# PiHAT_v0_4.net
KiCad netlist of a schematic drawn in EAGLE
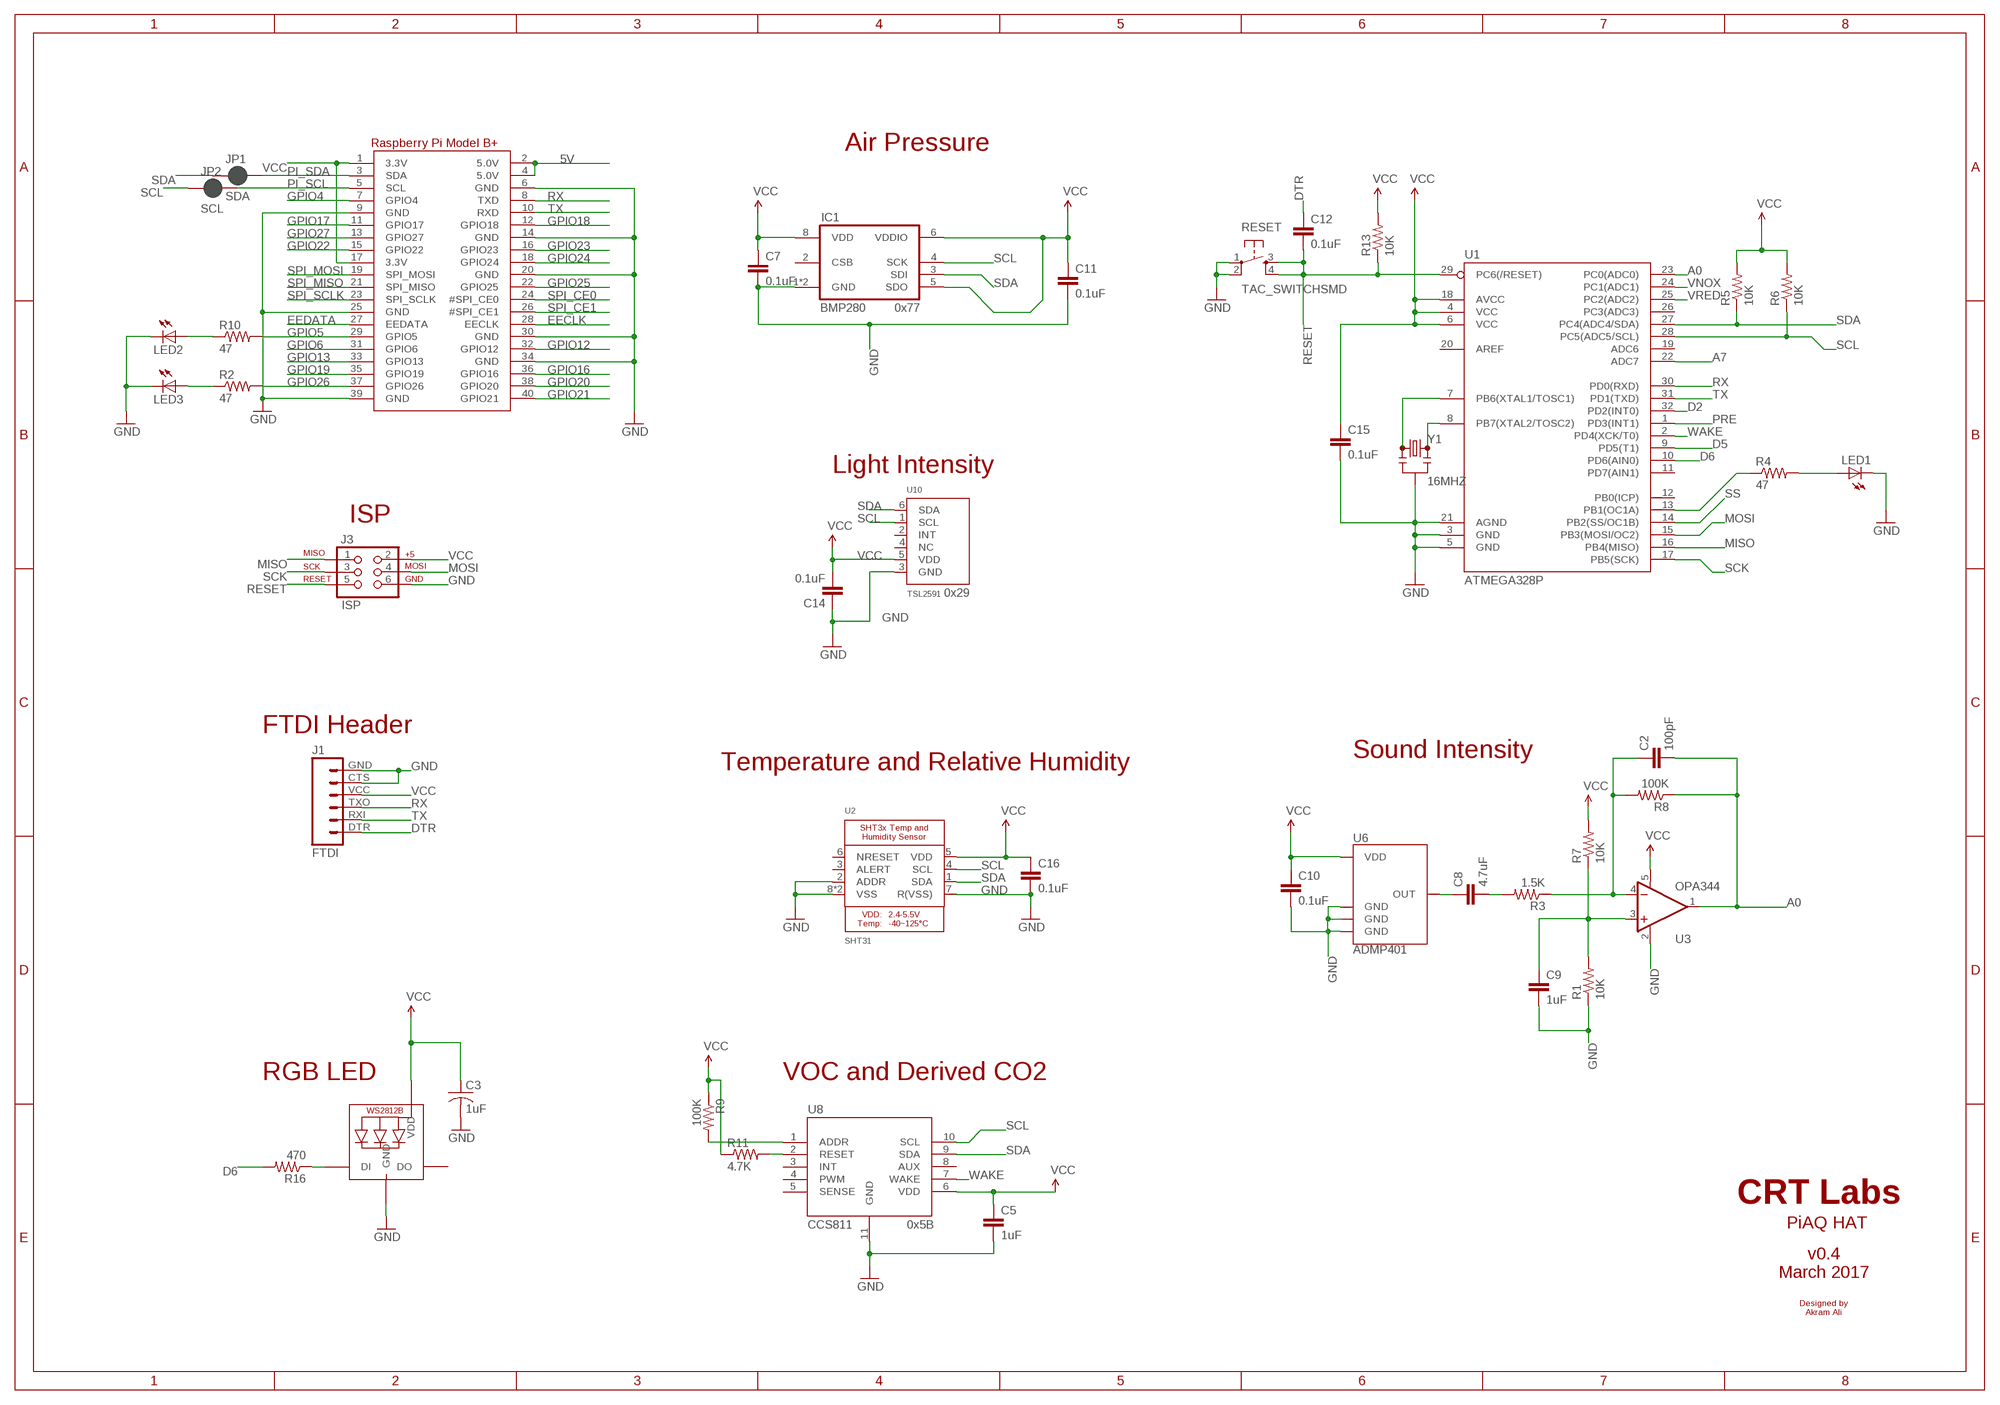
[diagram p0: schematic, sheet 1]

(export (version "E")
  (design (tool "Eeschema 10.0.6"))
  (components
    (comp (ref "C2")
      (value "100pF")
      (footprint "eagle-import:0805")
      (fields (field (name "MPN") "CC0805JRNPO9BN101"))
      (libsource (lib "eagle-import") (part "CAP0805"))
    )
    (comp (ref "C3")
      (value "1uF")
      (footprint "eagle-import:C0603K")
      (fields (field (name "MPN") "CC0805ZRY5V8BB105"))
      (libsource (lib "eagle-import") (part "C-USC0603K"))
    )
    (comp (ref "C5")
      (value "1uF")
      (footprint "eagle-import:0805")
      (fields (field (name "MPN") "CC0603KRX7R7BB104"))
      (libsource (lib "eagle-import") (part "SparkFun-Passives_CAP0805"))
    )
    (comp (ref "C7")
      (value "0.1uF")
      (footprint "eagle-import:0805")
      (fields (field (name "MPN") "CC0603KRX7R7BB104"))
      (libsource (lib "eagle-import") (part "SparkFun-Passives_CAP0805"))
    )
    (comp (ref "C8")
      (value "4.7uF")
      (footprint "eagle-import:0805")
      (fields (field (name "MPN") "CC0805KKX5R8BB475"))
      (libsource (lib "eagle-import") (part "CAP0805"))
    )
    (comp (ref "C9")
      (value "1uF")
      (footprint "eagle-import:0805")
      (fields (field (name "MPN") "CC0805KKX7R7BB105"))
      (libsource (lib "eagle-import") (part "CAP0805"))
    )
    (comp (ref "C10")
      (value "0.1uF")
      (footprint "eagle-import:0805")
      (fields (field (name "MPN") "CC0603KRX7R7BB104"))
      (libsource (lib "eagle-import") (part "CAP0805"))
    )
    (comp (ref "C11")
      (value "0.1uF")
      (footprint "eagle-import:0805")
      (fields (field (name "MPN") "CC0603KRX7R7BB104"))
      (libsource (lib "eagle-import") (part "SparkFun-Passives_CAP0805"))
    )
    (comp (ref "C12")
      (value "0.1uF")
      (footprint "eagle-import:0805")
      (fields (field (name "MPN") "CC0603KRX7R7BB104"))
      (libsource (lib "eagle-import") (part "SparkFun-Passives_CAP0805"))
    )
    (comp (ref "C14")
      (value "0.1uF")
      (footprint "eagle-import:0805")
      (fields (field (name "MPN") "CC0805KRX7R9BB104"))
      (libsource (lib "eagle-import") (part "SparkFun-Passives_CAP0805"))
    )
    (comp (ref "C15")
      (value "0.1uF")
      (footprint "eagle-import:0805")
      (fields (field (name "MPN") "CC0603KRX7R7BB104"))
      (libsource (lib "eagle-import") (part "SparkFun-Passives_CAP0805"))
    )
    (comp (ref "C16")
      (value "0.1uF")
      (footprint "eagle-import:0805")
      (fields (field (name "MPN") "CC0805KRX7R9BB104"))
      (libsource (lib "eagle-import") (part "SparkFun-Passives_CAP0805"))
    )
    (comp (ref "IC1")
      (value "BMP280")
      (footprint "eagle-import:BMP280")
      (libsource (lib "eagle-import") (part "BMP280"))
    )
    (comp (ref "J1")
      (value "FTDI")
      (footprint "eagle-import:FTDI_BASIC")
      (libsource (lib "eagle-import") (part "FTDI_BASICPTH"))
    )
    (comp (ref "J3")
      (value "ISP")
      (footprint "eagle-import:2X3")
      (libsource (lib "eagle-import") (part "AVR_SPI_PRG_6PTH"))
    )
    (comp (ref "JP1")
      (value "SDA")
      (footprint "eagle-import:PAD-JUMPER-2-NC_BY_PASTE_YES_SILK_FULL_BOX")
      (libsource (lib "eagle-import") (part "JUMPER-PAD-2-NC_BY_PASTEFULL-BOX-SILK"))
    )
    (comp (ref "JP2")
      (value "SCL")
      (footprint "eagle-import:PAD-JUMPER-2-NC_BY_PASTE_YES_SILK_FULL_BOX")
      (libsource (lib "eagle-import") (part "JUMPER-PAD-2-NC_BY_PASTEFULL-BOX-SILK"))
    )
    (comp (ref "LED1")
      (value "LEDCHIPLED_0805")
      (footprint "eagle-import:CHIPLED_0805")
      (fields (field (name "MPN") "LTST-C170TBKT"))
      (libsource (lib "eagle-import") (part "LEDCHIPLED_0805"))
    )
    (comp (ref "LED2")
      (value "LEDCHIPLED_0805")
      (footprint "eagle-import:CHIPLED_0805")
      (fields (field (name "MPN") "LTST-C170TBKT"))
      (libsource (lib "eagle-import") (part "LEDCHIPLED_0805"))
    )
    (comp (ref "LED3")
      (value "LEDCHIPLED_0805")
      (footprint "eagle-import:CHIPLED_0805")
      (fields (field (name "MPN") "LTST-C170TBKT"))
      (libsource (lib "eagle-import") (part "LEDCHIPLED_0805"))
    )
    (comp (ref "R1")
      (value "10K")
      (footprint "eagle-import:0805")
      (fields (field (name "MPN") "RC0805JR-0710KL"))
      (libsource (lib "eagle-import") (part "RESISTOR0805-RES"))
    )
    (comp (ref "R2")
      (value "47")
      (footprint "eagle-import:0805")
      (fields (field (name "MPN") "RC0805JR-0747RL"))
      (libsource (lib "eagle-import") (part "SparkFun-Resistors_RESISTOR0805-RES"))
    )
    (comp (ref "R3")
      (value "1.5K")
      (footprint "eagle-import:0805")
      (fields (field (name "MPN") "RT0805BRD071K5L"))
      (libsource (lib "eagle-import") (part "RESISTOR0805-RES"))
    )
    (comp (ref "R4")
      (value "47")
      (footprint "eagle-import:0805")
      (fields (field (name "MPN") "RC0805JR-0747RL"))
      (libsource (lib "eagle-import") (part "SparkFun-Resistors_RESISTOR0805-RES"))
    )
    (comp (ref "R5")
      (value "10K")
      (footprint "eagle-import:0805")
      (fields (field (name "MPN") "RC0805JR-0710KL"))
      (libsource (lib "eagle-import") (part "SparkFun-Resistors_RESISTOR0805-RES"))
    )
    (comp (ref "R6")
      (value "10K")
      (footprint "eagle-import:0805")
      (fields (field (name "MPN") "RC0805JR-0710KL"))
      (libsource (lib "eagle-import") (part "SparkFun-Resistors_RESISTOR0805-RES"))
    )
    (comp (ref "R7")
      (value "10K")
      (footprint "eagle-import:0805")
      (fields (field (name "MPN") "RC0805JR-0710KL"))
      (libsource (lib "eagle-import") (part "RESISTOR0805-RES"))
    )
    (comp (ref "R8")
      (value "100K")
      (footprint "eagle-import:0805")
      (fields (field (name "MPN") "RC0805FR-07100KL"))
      (libsource (lib "eagle-import") (part "RESISTOR0805-RES"))
    )
    (comp (ref "R9")
      (value "100K")
      (footprint "eagle-import:0805")
      (fields (field (name "MPN") "RC0805FR-07100KL"))
      (libsource (lib "eagle-import") (part "RESISTOR0805-RES"))
    )
    (comp (ref "R10")
      (value "47")
      (footprint "eagle-import:0805")
      (fields (field (name "MPN") "RC0805JR-0747RL"))
      (libsource (lib "eagle-import") (part "SparkFun-Resistors_RESISTOR0805-RES"))
    )
    (comp (ref "R11")
      (value "4.7K")
      (footprint "eagle-import:0805")
      (fields (field (name "MPN") "RC0805FR-07100KL"))
      (libsource (lib "eagle-import") (part "RESISTOR0805-RES"))
    )
    (comp (ref "R13")
      (value "10K")
      (footprint "eagle-import:0805")
      (fields (field (name "MPN") "RC0805JR-0710KL"))
      (libsource (lib "eagle-import") (part "RESISTOR0805-RES"))
    )
    (comp (ref "R16")
      (value "470")
      (footprint "eagle-import:R0603")
      (fields (field (name "MPN") "RC0805FR-07470RL "))
      (libsource (lib "eagle-import") (part "R-US_R0603"))
    )
    (comp (ref "RESET")
      (value "TAC_SWITCHSMD")
      (footprint "eagle-import:TACTILE-SWITCH-SMD")
      (fields (field (name "MPN") "PTS525SM15SMTR2 LFS"))
      (libsource (lib "eagle-import") (part "TAC_SWITCHSMD"))
    )
    (comp (ref "RGBLED")
      (value "WS2812B3535")
      (footprint "eagle-import:LED3535")
      (fields (field (name "MPN") "SK6812 mini"))
      (libsource (lib "eagle-import") (part "WS2812B3535"))
    )
    (comp (ref "RPI1")
      (value "RASPBERRYPI_BPLUS_HATSLOTS")
      (footprint "eagle-import:PI_HAT_SLOTS")
      (libsource (lib "eagle-import") (part "RASPBERRYPI_BPLUS_HATSLOTS"))
    )
    (comp (ref "U1")
      (value "ATMEGA328P")
      (footprint "eagle-import:TQFP32-08")
      (fields (field (name "MPN") "ATMEGA328PB-AU"))
      (libsource (lib "eagle-import") (part "ATMEGA328P_TQFP"))
    )
    (comp (ref "U2")
      (value "SHT31")
      (footprint "eagle-import:SHT3X")
      (fields (field (name "MPN") "SHT35-DIS-B"))
      (libsource (lib "eagle-import") (part "SHT3X"))
    )
    (comp (ref "U3")
      (value "OPA344")
      (footprint "eagle-import:SOT23-5")
      (fields (field (name "MPN") "OPA344NA/3K"))
      (libsource (lib "eagle-import") (part "OPA344"))
    )
    (comp (ref "U6")
      (value "ADMP401")
      (footprint "eagle-import:ADMP401")
      (fields (field (name "MPN") "INMP401ACEZ-R7"))
      (libsource (lib "eagle-import") (part "ADMP401"))
    )
    (comp (ref "U8")
      (value "CCS811")
      (footprint "eagle-import:LGA")
      (libsource (lib "eagle-import") (part "CCS811-I2C"))
    )
    (comp (ref "U10")
      (value "TSL2591")
      (footprint "eagle-import:DFN6_TAOS")
      (fields (field (name "MPN") "TSL25911FN "))
      (libsource (lib "eagle-import") (part "LIGHT_TSL2591"))
    )
    (comp (ref "Y1")
      (value "16MHZ")
      (footprint "eagle-import:RESONATOR-SMD")
      (fields (field (name "MPN") "CSTCE16M0V53-R0"))
      (libsource (lib "eagle-import") (part "RESONATOR16MHZ"))
    )
  )
  (nets
    (net (code "1") (name "/5V") (class "Default")
      (node (ref "RPI1") (pin "2") (pinfunction "5.0V_2") (pintype "power_in"))
      (node (ref "RPI1") (pin "4") (pinfunction "5.0V_4") (pintype "power_in"))
    )
    (net (code "2") (name "/EECLK") (class "Default")
      (node (ref "RPI1") (pin "28") (pinfunction "EECLK_28") (pintype "power_in"))
    )
    (net (code "3") (name "/EEDATA") (class "Default")
      (node (ref "RPI1") (pin "27") (pinfunction "EEDATA_27") (pintype "bidirectional"))
    )
    (net (code "4") (name "/GPIO4") (class "Default")
      (node (ref "RPI1") (pin "7") (pinfunction "GPIO4_7") (pintype "bidirectional"))
    )
    (net (code "5") (name "/GPIO5") (class "Default")
      (node (ref "R10") (pin "2") (pinfunction "2_2") (pintype "passive"))
      (node (ref "RPI1") (pin "29") (pinfunction "GPIO5_29") (pintype "bidirectional"))
    )
    (net (code "6") (name "/GPIO6") (class "Default")
      (node (ref "RPI1") (pin "31") (pinfunction "GPIO6_31") (pintype "power_in"))
    )
    (net (code "7") (name "/GPIO12") (class "Default")
      (node (ref "RPI1") (pin "32") (pinfunction "GPIO12_32") (pintype "bidirectional"))
    )
    (net (code "8") (name "/GPIO13") (class "Default")
      (node (ref "RPI1") (pin "33") (pinfunction "GPIO13_33") (pintype "bidirectional"))
    )
    (net (code "9") (name "/GPIO16") (class "Default")
      (node (ref "RPI1") (pin "36") (pinfunction "GPIO16_36") (pintype "power_in"))
    )
    (net (code "10") (name "/GPIO17") (class "Default")
      (node (ref "RPI1") (pin "11") (pinfunction "GPIO17_11") (pintype "bidirectional"))
    )
    (net (code "11") (name "/GPIO18") (class "Default")
      (node (ref "RPI1") (pin "12") (pinfunction "GPIO18_12") (pintype "bidirectional"))
    )
    (net (code "12") (name "/GPIO19") (class "Default")
      (node (ref "RPI1") (pin "35") (pinfunction "GPIO19_35") (pintype "bidirectional"))
    )
    (net (code "13") (name "/GPIO20") (class "Default")
      (node (ref "RPI1") (pin "38") (pinfunction "GPIO20_38") (pintype "bidirectional"))
    )
    (net (code "14") (name "/GPIO21") (class "Default")
      (node (ref "RPI1") (pin "40") (pinfunction "GPIO21_40") (pintype "bidirectional"))
    )
    (net (code "15") (name "/GPIO22") (class "Default")
      (node (ref "RPI1") (pin "15") (pinfunction "GPIO22_15") (pintype "bidirectional"))
    )
    (net (code "16") (name "/GPIO23") (class "Default")
      (node (ref "RPI1") (pin "16") (pinfunction "GPIO23_16") (pintype "bidirectional"))
    )
    (net (code "17") (name "/GPIO24") (class "Default")
      (node (ref "RPI1") (pin "18") (pinfunction "GPIO24_18") (pintype "bidirectional"))
    )
    (net (code "18") (name "/GPIO25") (class "Default")
      (node (ref "RPI1") (pin "22") (pinfunction "GPIO25_22") (pintype "bidirectional"))
    )
    (net (code "19") (name "/GPIO26") (class "Default")
      (node (ref "R2") (pin "2") (pinfunction "2_2") (pintype "passive"))
      (node (ref "RPI1") (pin "37") (pinfunction "GPIO26_37") (pintype "bidirectional"))
    )
    (net (code "20") (name "/GPIO27") (class "Default")
      (node (ref "RPI1") (pin "13") (pinfunction "GPIO27_13") (pintype "bidirectional"))
    )
    (net (code "21") (name "/PI_SCL") (class "Default")
      (node (ref "JP2") (pin "2") (pinfunction "2_2") (pintype "passive"))
      (node (ref "RPI1") (pin "5") (pinfunction "SCL_5") (pintype "bidirectional"))
    )
    (net (code "22") (name "/PI_SDA") (class "Default")
      (node (ref "JP1") (pin "2") (pinfunction "2_2") (pintype "passive"))
      (node (ref "RPI1") (pin "3") (pinfunction "SDA_3") (pintype "bidirectional"))
    )
    (net (code "23") (name "/SPI_CE0") (class "Default")
      (node (ref "RPI1") (pin "24") (pinfunction "#SPI_CE0_24") (pintype "bidirectional"))
    )
    (net (code "24") (name "/SPI_CE1") (class "Default")
      (node (ref "RPI1") (pin "26") (pinfunction "#SPI_CE1_26") (pintype "bidirectional"))
    )
    (net (code "25") (name "/SPI_MISO") (class "Default")
      (node (ref "RPI1") (pin "21") (pinfunction "SPI_MISO_21") (pintype "bidirectional"))
    )
    (net (code "26") (name "/SPI_MOSI") (class "Default")
      (node (ref "RPI1") (pin "19") (pinfunction "SPI_MOSI_19") (pintype "bidirectional"))
    )
    (net (code "27") (name "/SPI_SCLK") (class "Default")
      (node (ref "RPI1") (pin "23") (pinfunction "SPI_SCLK_23") (pintype "bidirectional"))
    )
    (net (code "28") (name "A0") (class "Default")
      (node (ref "C2") (pin "2") (pinfunction "2_2") (pintype "passive"))
      (node (ref "R8") (pin "1") (pinfunction "1_1") (pintype "passive"))
      (node (ref "U1") (pin "23") (pinfunction "PC0(ADC0)_23") (pintype "bidirectional"))
      (node (ref "U3") (pin "1") (pinfunction "OUT_1") (pintype "output"))
    )
    (net (code "29") (name "A7") (class "Default")
      (node (ref "U1") (pin "22") (pinfunction "ADC7_22") (pintype "bidirectional"))
    )
    (net (code "30") (name "D2") (class "Default")
      (node (ref "U1") (pin "32") (pinfunction "PD2(INT0)_32") (pintype "bidirectional"))
    )
    (net (code "31") (name "D5") (class "Default")
      (node (ref "U1") (pin "9") (pinfunction "PD5(T1)_9") (pintype "bidirectional"))
    )
    (net (code "32") (name "D6") (class "Default")
      (node (ref "R16") (pin "2") (pinfunction "2_2") (pintype "passive"))
      (node (ref "U1") (pin "10") (pinfunction "PD6(AIN0)_10") (pintype "bidirectional"))
    )
    (net (code "33") (name "DTR") (class "Default")
      (node (ref "C12") (pin "1") (pinfunction "1_1") (pintype "passive"))
      (node (ref "J1") (pin "DTR") (pinfunction "1_DTR") (pintype "passive"))
    )
    (net (code "34") (name "GND") (class "Default")
      (node (ref "C10") (pin "2") (pinfunction "2_2") (pintype "passive"))
      (node (ref "C11") (pin "2") (pinfunction "2_2") (pintype "passive"))
      (node (ref "C14") (pin "1") (pinfunction "1_1") (pintype "passive"))
      (node (ref "C15") (pin "2") (pinfunction "2_2") (pintype "passive"))
      (node (ref "C16") (pin "2") (pinfunction "2_2") (pintype "passive"))
      (node (ref "C3") (pin "2") (pinfunction "2_2") (pintype "passive"))
      (node (ref "C5") (pin "2") (pinfunction "2_2") (pintype "passive"))
      (node (ref "C7") (pin "2") (pinfunction "2_2") (pintype "passive"))
      (node (ref "C9") (pin "2") (pinfunction "2_2") (pintype "passive"))
      (node (ref "IC1") (pin "1") (pinfunction "GND_1") (pintype "power_in"))
      (node (ref "IC1") (pin "7") (pinfunction "GND_7") (pintype "power_in"))
      (node (ref "J1") (pin "CTS") (pinfunction "5_CTS") (pintype "passive"))
      (node (ref "J1") (pin "GND") (pinfunction "6_GND") (pintype "passive"))
      (node (ref "J3") (pin "6") (pinfunction "6_6") (pintype "passive"))
      (node (ref "LED1") (pin "C") (pinfunction "C_C") (pintype "passive"))
      (node (ref "LED2") (pin "C") (pinfunction "C_C") (pintype "passive"))
      (node (ref "LED3") (pin "C") (pinfunction "C_C") (pintype "passive"))
      (node (ref "R1") (pin "1") (pinfunction "1_1") (pintype "passive"))
      (node (ref "RESET") (pin "1") (pinfunction "1_1") (pintype "passive"))
      (node (ref "RESET") (pin "2") (pinfunction "2_2") (pintype "passive"))
      (node (ref "RGBLED") (pin "4") (pinfunction "GND_4") (pintype "power_in"))
      (node (ref "RPI1") (pin "14") (pinfunction "GND_14") (pintype "power_in"))
      (node (ref "RPI1") (pin "20") (pinfunction "GND_20") (pintype "power_in"))
      (node (ref "RPI1") (pin "25") (pinfunction "GND_25") (pintype "power_in"))
      (node (ref "RPI1") (pin "30") (pinfunction "GND_30") (pintype "bidirectional"))
      (node (ref "RPI1") (pin "34") (pinfunction "GND_34") (pintype "bidirectional"))
      (node (ref "RPI1") (pin "39") (pinfunction "GND_39") (pintype "power_in"))
      (node (ref "RPI1") (pin "6") (pinfunction "GND_6") (pintype "power_in"))
      (node (ref "RPI1") (pin "9") (pinfunction "GND_9") (pintype "power_in"))
      (node (ref "U1") (pin "21") (pinfunction "AGND_21") (pintype "bidirectional"))
      (node (ref "U1") (pin "3") (pinfunction "GND_3") (pintype "bidirectional"))
      (node (ref "U1") (pin "5") (pinfunction "GND_5") (pintype "bidirectional"))
      (node (ref "U10") (pin "3") (pinfunction "GND_3") (pintype "power_in"))
      (node (ref "U2") (pin "2") (pinfunction "ADDR_2") (pintype "bidirectional"))
      (node (ref "U2") (pin "7") (pinfunction "R(VSS)_7") (pintype "bidirectional"))
      (node (ref "U2") (pin "8") (pinfunction "VSS_8") (pintype "power_in"))
      (node (ref "U2") (pin "THERMAL") (pinfunction "VSS_THERMAL") (pintype "power_in"))
      (node (ref "U3") (pin "2") (pinfunction "V-_2") (pintype "power_in"))
      (node (ref "U6") (pin "2") (pinfunction "GND_2") (pintype "bidirectional"))
      (node (ref "U6") (pin "4") (pinfunction "GND_4") (pintype "bidirectional"))
      (node (ref "U6") (pin "6") (pinfunction "GND_6") (pintype "bidirectional"))
      (node (ref "U8") (pin "11") (pinfunction "GND_11") (pintype "bidirectional"))
      (node (ref "Y1") (pin "2") (pinfunction "2_2") (pintype "passive"))
    )
    (net (code "35") (name "MISO") (class "Default")
      (node (ref "J3") (pin "1") (pinfunction "1_1") (pintype "passive"))
      (node (ref "U1") (pin "16") (pinfunction "PB4(MISO)_16") (pintype "bidirectional"))
    )
    (net (code "36") (name "MOSI") (class "Default")
      (node (ref "J3") (pin "4") (pinfunction "4_4") (pintype "passive"))
      (node (ref "U1") (pin "15") (pinfunction "PB3(MOSI/OC2)_15") (pintype "bidirectional"))
    )
    (net (code "37") (name "Net-(C8-Pad2)") (class "Default")
      (node (ref "C8") (pin "2") (pinfunction "2_2") (pintype "passive"))
      (node (ref "R3") (pin "2") (pinfunction "2_2") (pintype "passive"))
    )
    (net (code "38") (name "Net-(LED1-PadA)") (class "Default")
      (node (ref "LED1") (pin "A") (pinfunction "A_A") (pintype "passive"))
      (node (ref "R4") (pin "2") (pinfunction "2_2") (pintype "passive"))
    )
    (net (code "39") (name "Net-(LED2-PadA)") (class "Default")
      (node (ref "LED2") (pin "A") (pinfunction "A_A") (pintype "passive"))
      (node (ref "R10") (pin "1") (pinfunction "1_1") (pintype "passive"))
    )
    (net (code "40") (name "Net-(LED3-PadA)") (class "Default")
      (node (ref "LED3") (pin "A") (pinfunction "A_A") (pintype "passive"))
      (node (ref "R2") (pin "1") (pinfunction "1_1") (pintype "passive"))
    )
    (net (code "41") (name "Net-(RGBLED-DI)") (class "Default")
      (node (ref "R16") (pin "1") (pinfunction "1_1") (pintype "passive"))
      (node (ref "RGBLED") (pin "1") (pinfunction "DI_1") (pintype "input"))
    )
    (net (code "42") (name "Net-(U1-PB1(OC1A))") (class "Default")
      (node (ref "R4") (pin "1") (pinfunction "1_1") (pintype "passive"))
      (node (ref "U1") (pin "13") (pinfunction "PB1(OC1A)_13") (pintype "bidirectional"))
    )
    (net (code "43") (name "Net-(U1-PB6(XTAL1{slash}TOSC1))") (class "Default")
      (node (ref "U1") (pin "7") (pinfunction "PB6(XTAL1/TOSC1)_7") (pintype "bidirectional"))
      (node (ref "Y1") (pin "1") (pinfunction "1_1") (pintype "passive"))
    )
    (net (code "44") (name "Net-(U1-PB7(XTAL2{slash}TOSC2))") (class "Default")
      (node (ref "U1") (pin "8") (pinfunction "PB7(XTAL2/TOSC2)_8") (pintype "bidirectional"))
      (node (ref "Y1") (pin "3") (pinfunction "3_3") (pintype "passive"))
    )
    (net (code "45") (name "Net-(U3-+IN)") (class "Default")
      (node (ref "C9") (pin "1") (pinfunction "1_1") (pintype "passive"))
      (node (ref "R1") (pin "2") (pinfunction "2_2") (pintype "passive"))
      (node (ref "R7") (pin "1") (pinfunction "1_1") (pintype "passive"))
      (node (ref "U3") (pin "3") (pinfunction "+IN_3") (pintype "input"))
    )
    (net (code "46") (name "Net-(U3--IN)") (class "Default")
      (node (ref "C2") (pin "1") (pinfunction "1_1") (pintype "passive"))
      (node (ref "R3") (pin "1") (pinfunction "1_1") (pintype "passive"))
      (node (ref "R8") (pin "2") (pinfunction "2_2") (pintype "passive"))
      (node (ref "U3") (pin "4") (pinfunction "-IN_4") (pintype "input"))
    )
    (net (code "47") (name "Net-(U6-OUT)") (class "Default")
      (node (ref "C8") (pin "1") (pinfunction "1_1") (pintype "passive"))
      (node (ref "U6") (pin "1") (pinfunction "OUT_1") (pintype "bidirectional"))
    )
    (net (code "48") (name "Net-(U8-ADDR)") (class "Default")
      (node (ref "R9") (pin "2") (pinfunction "2_2") (pintype "passive"))
      (node (ref "U8") (pin "1") (pinfunction "ADDR_1") (pintype "bidirectional"))
    )
    (net (code "49") (name "Net-(U8-RESET)") (class "Default")
      (node (ref "R11") (pin "2") (pinfunction "2_2") (pintype "passive"))
      (node (ref "U8") (pin "2") (pinfunction "RESET_2") (pintype "bidirectional"))
    )
    (net (code "50") (name "PRE") (class "Default")
      (node (ref "U1") (pin "1") (pinfunction "PD3(INT1)_1") (pintype "bidirectional"))
    )
    (net (code "51") (name "RESET") (class "Default")
      (node (ref "C12") (pin "2") (pinfunction "2_2") (pintype "passive"))
      (node (ref "J3") (pin "5") (pinfunction "5_5") (pintype "passive"))
      (node (ref "R13") (pin "1") (pinfunction "1_1") (pintype "passive"))
      (node (ref "RESET") (pin "3") (pinfunction "3_3") (pintype "passive"))
      (node (ref "RESET") (pin "4") (pinfunction "4_4") (pintype "passive"))
      (node (ref "U1") (pin "29") (pinfunction "PC6(/RESET)_29") (pintype "bidirectional"))
    )
    (net (code "52") (name "RX") (class "Default")
      (node (ref "J1") (pin "TXO") (pinfunction "3_TXO") (pintype "passive"))
      (node (ref "RPI1") (pin "8") (pinfunction "TXD_8") (pintype "output"))
      (node (ref "U1") (pin "30") (pinfunction "PD0(RXD)_30") (pintype "bidirectional"))
    )
    (net (code "53") (name "SCK") (class "Default")
      (node (ref "J3") (pin "3") (pinfunction "3_3") (pintype "passive"))
      (node (ref "U1") (pin "17") (pinfunction "PB5(SCK)_17") (pintype "bidirectional"))
    )
    (net (code "54") (name "SCL") (class "Default")
      (node (ref "IC1") (pin "4") (pinfunction "SCK_4") (pintype "bidirectional"))
      (node (ref "JP2") (pin "1") (pinfunction "1_1") (pintype "passive"))
      (node (ref "R6") (pin "1") (pinfunction "1_1") (pintype "passive"))
      (node (ref "U1") (pin "28") (pinfunction "PC5(ADC5/SCL)_28") (pintype "bidirectional"))
      (node (ref "U10") (pin "1") (pinfunction "SCL_1") (pintype "bidirectional"))
      (node (ref "U2") (pin "4") (pinfunction "SCL_4") (pintype "bidirectional"))
      (node (ref "U8") (pin "10") (pinfunction "SCL_10") (pintype "bidirectional"))
    )
    (net (code "55") (name "SDA") (class "Default")
      (node (ref "IC1") (pin "3") (pinfunction "SDI_3") (pintype "bidirectional"))
      (node (ref "JP1") (pin "1") (pinfunction "1_1") (pintype "passive"))
      (node (ref "R5") (pin "1") (pinfunction "1_1") (pintype "passive"))
      (node (ref "U1") (pin "27") (pinfunction "PC4(ADC4/SDA)_27") (pintype "bidirectional"))
      (node (ref "U10") (pin "6") (pinfunction "SDA_6") (pintype "bidirectional"))
      (node (ref "U2") (pin "1") (pinfunction "SDA_1") (pintype "bidirectional"))
      (node (ref "U8") (pin "9") (pinfunction "SDA_9") (pintype "bidirectional"))
    )
    (net (code "56") (name "SS") (class "Default")
      (node (ref "U1") (pin "14") (pinfunction "PB2(SS/OC1B)_14") (pintype "bidirectional"))
    )
    (net (code "57") (name "TX") (class "Default")
      (node (ref "J1") (pin "RXI") (pinfunction "2_RXI") (pintype "passive"))
      (node (ref "RPI1") (pin "10") (pinfunction "RXD_10") (pintype "bidirectional"))
      (node (ref "U1") (pin "31") (pinfunction "PD1(TXD)_31") (pintype "bidirectional"))
    )
    (net (code "58") (name "VCC") (class "Default")
      (node (ref "C10") (pin "1") (pinfunction "1_1") (pintype "passive"))
      (node (ref "C11") (pin "1") (pinfunction "1_1") (pintype "passive"))
      (node (ref "C14") (pin "2") (pinfunction "2_2") (pintype "passive"))
      (node (ref "C15") (pin "1") (pinfunction "1_1") (pintype "passive"))
      (node (ref "C16") (pin "1") (pinfunction "1_1") (pintype "passive"))
      (node (ref "C3") (pin "1") (pinfunction "1_1") (pintype "passive"))
      (node (ref "C5") (pin "1") (pinfunction "1_1") (pintype "passive"))
      (node (ref "C7") (pin "1") (pinfunction "1_1") (pintype "passive"))
      (node (ref "IC1") (pin "5") (pinfunction "SDO_5") (pintype "input"))
      (node (ref "IC1") (pin "6") (pinfunction "VDDIO_6") (pintype "power_in"))
      (node (ref "IC1") (pin "8") (pinfunction "VDD_8") (pintype "power_in"))
      (node (ref "J1") (pin "VCC") (pinfunction "4_VCC") (pintype "passive"))
      (node (ref "J3") (pin "2") (pinfunction "2_2") (pintype "passive"))
      (node (ref "R11") (pin "1") (pinfunction "1_1") (pintype "passive"))
      (node (ref "R13") (pin "2") (pinfunction "2_2") (pintype "passive"))
      (node (ref "R5") (pin "2") (pinfunction "2_2") (pintype "passive"))
      (node (ref "R6") (pin "2") (pinfunction "2_2") (pintype "passive"))
      (node (ref "R7") (pin "2") (pinfunction "2_2") (pintype "passive"))
      (node (ref "R9") (pin "1") (pinfunction "1_1") (pintype "passive"))
      (node (ref "RGBLED") (pin "2") (pinfunction "VDD_2") (pintype "power_in"))
      (node (ref "RPI1") (pin "1") (pinfunction "3.3V_1") (pintype "power_in"))
      (node (ref "RPI1") (pin "17") (pinfunction "3.3V_17") (pintype "power_in"))
      (node (ref "U1") (pin "18") (pinfunction "AVCC_18") (pintype "bidirectional"))
      (node (ref "U1") (pin "4") (pinfunction "VCC_4") (pintype "bidirectional"))
      (node (ref "U1") (pin "6") (pinfunction "VCC_6") (pintype "bidirectional"))
      (node (ref "U10") (pin "5") (pinfunction "VDD_5") (pintype "power_in"))
      (node (ref "U2") (pin "5") (pinfunction "VDD_5") (pintype "power_in"))
      (node (ref "U3") (pin "5") (pinfunction "V+_5") (pintype "power_in"))
      (node (ref "U6") (pin "5") (pinfunction "VDD_5") (pintype "bidirectional"))
      (node (ref "U8") (pin "6") (pinfunction "VDD_6") (pintype "bidirectional"))
    )
    (net (code "59") (name "VNOX") (class "Default")
      (node (ref "U1") (pin "24") (pinfunction "PC1(ADC1)_24") (pintype "bidirectional"))
    )
    (net (code "60") (name "VRED") (class "Default")
      (node (ref "U1") (pin "25") (pinfunction "PC2(ADC2)_25") (pintype "bidirectional"))
    )
    (net (code "61") (name "WAKE") (class "Default")
      (node (ref "U1") (pin "2") (pinfunction "PD4(XCK/T0)_2") (pintype "bidirectional"))
      (node (ref "U8") (pin "7") (pinfunction "WAKE_7") (pintype "bidirectional"))
    )
    (net (code "62") (name "unconnected-(IC1-CSB-Pad2)") (class "Default")
      (node (ref "IC1") (pin "2") (pinfunction "CSB_2") (pintype "input"))
    )
    (net (code "63") (name "unconnected-(RGBLED-DO-Pad3)") (class "Default")
      (node (ref "RGBLED") (pin "3") (pinfunction "DO_3") (pintype "output"))
    )
    (net (code "64") (name "unconnected-(U1-ADC6-Pad19)") (class "Default")
      (node (ref "U1") (pin "19") (pinfunction "ADC6_19") (pintype "bidirectional"))
    )
    (net (code "65") (name "unconnected-(U1-AREF-Pad20)") (class "Default")
      (node (ref "U1") (pin "20") (pinfunction "AREF_20") (pintype "bidirectional"))
    )
    (net (code "66") (name "unconnected-(U1-PB0(ICP)-Pad12)") (class "Default")
      (node (ref "U1") (pin "12") (pinfunction "PB0(ICP)_12") (pintype "bidirectional"))
    )
    (net (code "67") (name "unconnected-(U1-PC3(ADC3)-Pad26)") (class "Default")
      (node (ref "U1") (pin "26") (pinfunction "PC3(ADC3)_26") (pintype "bidirectional"))
    )
    (net (code "68") (name "unconnected-(U1-PD7(AIN1)-Pad11)") (class "Default")
      (node (ref "U1") (pin "11") (pinfunction "PD7(AIN1)_11") (pintype "bidirectional"))
    )
    (net (code "69") (name "unconnected-(U2-ALERT-Pad3)") (class "Default")
      (node (ref "U2") (pin "3") (pinfunction "ALERT_3") (pintype "bidirectional"))
    )
    (net (code "70") (name "unconnected-(U2-NRESET-Pad6)") (class "Default")
      (node (ref "U2") (pin "6") (pinfunction "NRESET_6") (pintype "bidirectional"))
    )
    (net (code "71") (name "unconnected-(U8-AUX-Pad8)") (class "Default")
      (node (ref "U8") (pin "8") (pinfunction "AUX_8") (pintype "bidirectional"))
    )
    (net (code "72") (name "unconnected-(U8-INT-Pad3)") (class "Default")
      (node (ref "U8") (pin "3") (pinfunction "INT_3") (pintype "bidirectional"))
    )
    (net (code "73") (name "unconnected-(U8-PWM-Pad4)") (class "Default")
      (node (ref "U8") (pin "4") (pinfunction "PWM_4") (pintype "bidirectional"))
    )
    (net (code "74") (name "unconnected-(U8-SENSE-Pad5)") (class "Default")
      (node (ref "U8") (pin "5") (pinfunction "SENSE_5") (pintype "bidirectional"))
    )
    (net (code "75") (name "unconnected-(U10-INT-Pad2)") (class "Default")
      (node (ref "U10") (pin "2") (pinfunction "INT_2") (pintype "output"))
    )
    (net (code "76") (name "unconnected-(U10-NC-Pad4)") (class "Default")
      (node (ref "U10") (pin "4") (pinfunction "NC_4") (pintype "no_connect"))
    )
  )
)
